# feelerBox1_2_3.net
KiCad netlist of a schematic drawn in EAGLE
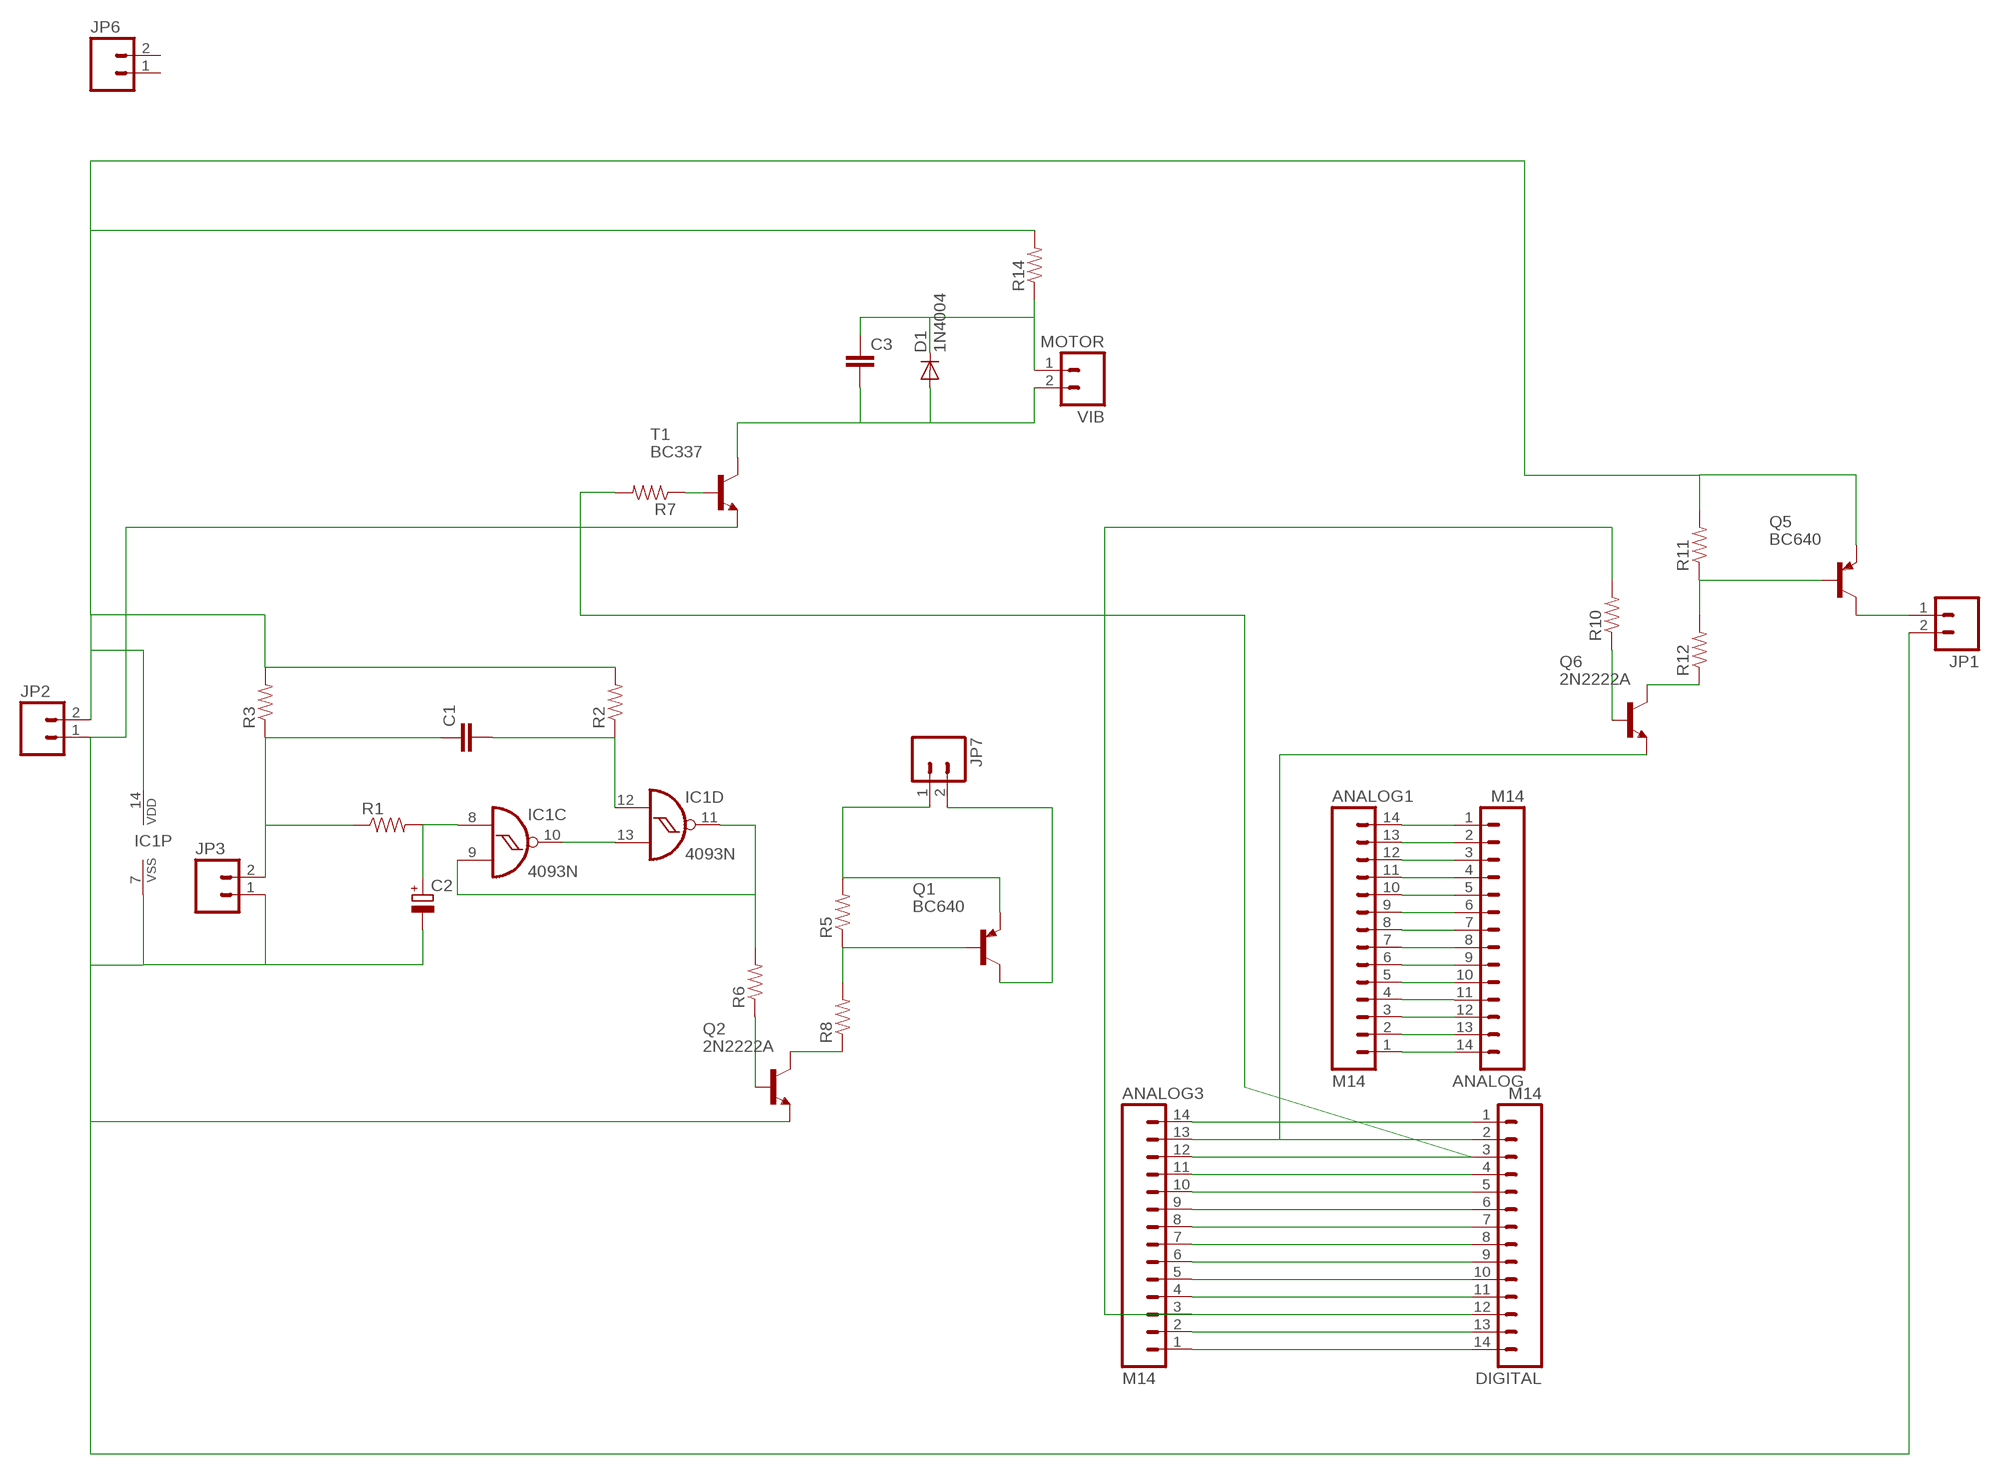
[diagram p0: schematic, sheet 1]

(export (version "E")
  (design (tool "Eeschema 10.0.6"))
  (components
    (comp (ref "ANALOG")
      (value "M14")
      (footprint "eagle-import:1X14")
      (libsource (lib "eagle-import") (part "M14"))
    )
    (comp (ref "ANALOG1")
      (value "M14")
      (footprint "eagle-import:1X14")
      (libsource (lib "eagle-import") (part "M14"))
    )
    (comp (ref "ANALOG3")
      (value "M14")
      (footprint "eagle-import:1X14")
      (libsource (lib "eagle-import") (part "M14"))
    )
    (comp (ref "C1")
      (value "0.1UF-50V-20%(PTH)KIT-EZ")
      (footprint "eagle-import:CAP-PTH-SMALL-KIT")
      (libsource (lib "eagle-import") (part "0.1UF-50V-20%(PTH)KIT-EZ"))
    )
    (comp (ref "C2")
      (value "CPOL-EUE2.5-5")
      (footprint "eagle-import:E2,5-5")
      (libsource (lib "eagle-import") (part "CPOL-EUE2.5-5"))
    )
    (comp (ref "C3")
      (value "CAPKIT")
      (footprint "eagle-import:CAP-PTH-SMALL-KIT")
      (libsource (lib "eagle-import") (part "CAPKIT"))
    )
    (comp (ref "D1")
      (value "1N4004")
      (footprint "eagle-import:DO41-10")
      (libsource (lib "eagle-import") (part "1N4004"))
    )
    (comp (ref "DIGITAL")
      (value "M14")
      (footprint "eagle-import:1X14")
      (libsource (lib "eagle-import") (part "M14"))
    )
    (comp (ref "IC1")
      (value "4093N")
      (footprint "eagle-import:DIL14")
      (libsource (lib "eagle-import") (part "4093N"))
    )
    (comp (ref "JP1")
      (value "M02PTH")
      (footprint "eagle-import:1X02")
      (libsource (lib "eagle-import") (part "M02PTH"))
    )
    (comp (ref "JP2")
      (value "M02PTH")
      (footprint "eagle-import:1X02")
      (libsource (lib "eagle-import") (part "M02PTH"))
    )
    (comp (ref "JP3")
      (value "M02PTH")
      (footprint "eagle-import:1X02")
      (libsource (lib "eagle-import") (part "M02PTH"))
    )
    (comp (ref "JP6")
      (value "M02PTH")
      (footprint "eagle-import:1X02")
      (libsource (lib "eagle-import") (part "M02PTH"))
    )
    (comp (ref "JP7")
      (value "M02PTH")
      (footprint "eagle-import:1X02")
      (libsource (lib "eagle-import") (part "M02PTH"))
    )
    (comp (ref "Q1")
      (value "BC640")
      (footprint "eagle-import:TO92-BCE")
      (libsource (lib "eagle-import") (part "BC640"))
    )
    (comp (ref "Q2")
      (value "2N2222A")
      (footprint "eagle-import:TO18")
      (libsource (lib "eagle-import") (part "2N2222A"))
    )
    (comp (ref "Q5")
      (value "BC640")
      (footprint "eagle-import:TO92-BCE")
      (libsource (lib "eagle-import") (part "BC640"))
    )
    (comp (ref "Q6")
      (value "2N2222A")
      (footprint "eagle-import:TO18")
      (libsource (lib "eagle-import") (part "2N2222A"))
    )
    (comp (ref "R1")
      (value "RESISTORAXIAL-0.3")
      (footprint "eagle-import:AXIAL-0.3")
      (libsource (lib "eagle-import") (part "RESISTORAXIAL-0.3"))
    )
    (comp (ref "R2")
      (value "RESISTORAXIAL-0.3")
      (footprint "eagle-import:AXIAL-0.3")
      (libsource (lib "eagle-import") (part "RESISTORAXIAL-0.3"))
    )
    (comp (ref "R3")
      (value "RESISTORAXIAL-0.3")
      (footprint "eagle-import:AXIAL-0.3")
      (libsource (lib "eagle-import") (part "RESISTORAXIAL-0.3"))
    )
    (comp (ref "R5")
      (value "RESISTORPTH-1/4W-VERT")
      (footprint "eagle-import:AXIAL-0.1")
      (libsource (lib "eagle-import") (part "RESISTORPTH-1/4W-VERT"))
    )
    (comp (ref "R6")
      (value "RESISTORAXIAL-0.3")
      (footprint "eagle-import:AXIAL-0.3")
      (libsource (lib "eagle-import") (part "RESISTORAXIAL-0.3"))
    )
    (comp (ref "R7")
      (value "RESISTORAXIAL-0.3")
      (footprint "eagle-import:AXIAL-0.3")
      (libsource (lib "eagle-import") (part "RESISTORAXIAL-0.3"))
    )
    (comp (ref "R8")
      (value "RESISTORAXIAL-0.3")
      (footprint "eagle-import:AXIAL-0.3")
      (libsource (lib "eagle-import") (part "RESISTORAXIAL-0.3"))
    )
    (comp (ref "R10")
      (value "RESISTORPTH-1/4W-VERT")
      (footprint "eagle-import:AXIAL-0.1")
      (libsource (lib "eagle-import") (part "RESISTORPTH-1/4W-VERT"))
    )
    (comp (ref "R11")
      (value "RESISTORPTH-1/4W-VERT")
      (footprint "eagle-import:AXIAL-0.1")
      (libsource (lib "eagle-import") (part "RESISTORPTH-1/4W-VERT"))
    )
    (comp (ref "R12")
      (value "RESISTORPTH-1/4W-VERT")
      (footprint "eagle-import:AXIAL-0.1")
      (libsource (lib "eagle-import") (part "RESISTORPTH-1/4W-VERT"))
    )
    (comp (ref "R14")
      (value "RESISTORPTH-1/4W-VERT")
      (footprint "eagle-import:AXIAL-0.1")
      (libsource (lib "eagle-import") (part "RESISTORPTH-1/4W-VERT"))
    )
    (comp (ref "T1")
      (value "BC337")
      (footprint "eagle-import:TO92")
      (libsource (lib "eagle-import") (part "BC337"))
    )
    (comp (ref "VIB")
      (value "MOTOR")
      (footprint "eagle-import:1X02")
      (libsource (lib "eagle-import") (part "M02PTH"))
    )
  )
  (nets
    (net (code "1") (name "Net-(ANALOG-Pad1)") (class "Default")
      (node (ref "ANALOG") (pin "1") (pinfunction "1_1") (pintype "passive"))
      (node (ref "ANALOG1") (pin "14") (pinfunction "14_14") (pintype "passive"))
    )
    (net (code "2") (name "Net-(ANALOG-Pad2)") (class "Default")
      (node (ref "ANALOG") (pin "2") (pinfunction "2_2") (pintype "passive"))
      (node (ref "ANALOG1") (pin "13") (pinfunction "13_13") (pintype "passive"))
    )
    (net (code "3") (name "Net-(ANALOG-Pad3)") (class "Default")
      (node (ref "ANALOG") (pin "3") (pinfunction "3_3") (pintype "passive"))
      (node (ref "ANALOG1") (pin "12") (pinfunction "12_12") (pintype "passive"))
    )
    (net (code "4") (name "Net-(ANALOG-Pad4)") (class "Default")
      (node (ref "ANALOG") (pin "4") (pinfunction "4_4") (pintype "passive"))
      (node (ref "ANALOG1") (pin "11") (pinfunction "11_11") (pintype "passive"))
    )
    (net (code "5") (name "Net-(ANALOG-Pad5)") (class "Default")
      (node (ref "ANALOG") (pin "5") (pinfunction "5_5") (pintype "passive"))
      (node (ref "ANALOG1") (pin "10") (pinfunction "10_10") (pintype "passive"))
    )
    (net (code "6") (name "Net-(ANALOG-Pad6)") (class "Default")
      (node (ref "ANALOG") (pin "6") (pinfunction "6_6") (pintype "passive"))
      (node (ref "ANALOG1") (pin "9") (pinfunction "9_9") (pintype "passive"))
    )
    (net (code "7") (name "Net-(ANALOG-Pad7)") (class "Default")
      (node (ref "ANALOG") (pin "7") (pinfunction "7_7") (pintype "passive"))
      (node (ref "ANALOG1") (pin "8") (pinfunction "8_8") (pintype "passive"))
    )
    (net (code "8") (name "Net-(ANALOG-Pad8)") (class "Default")
      (node (ref "ANALOG") (pin "8") (pinfunction "8_8") (pintype "passive"))
      (node (ref "ANALOG1") (pin "7") (pinfunction "7_7") (pintype "passive"))
    )
    (net (code "9") (name "Net-(ANALOG-Pad9)") (class "Default")
      (node (ref "ANALOG") (pin "9") (pinfunction "9_9") (pintype "passive"))
      (node (ref "ANALOG1") (pin "6") (pinfunction "6_6") (pintype "passive"))
    )
    (net (code "10") (name "Net-(ANALOG-Pad10)") (class "Default")
      (node (ref "ANALOG") (pin "10") (pinfunction "10_10") (pintype "passive"))
      (node (ref "ANALOG1") (pin "5") (pinfunction "5_5") (pintype "passive"))
    )
    (net (code "11") (name "Net-(ANALOG-Pad11)") (class "Default")
      (node (ref "ANALOG") (pin "11") (pinfunction "11_11") (pintype "passive"))
      (node (ref "ANALOG1") (pin "4") (pinfunction "4_4") (pintype "passive"))
    )
    (net (code "12") (name "Net-(ANALOG-Pad12)") (class "Default")
      (node (ref "ANALOG") (pin "12") (pinfunction "12_12") (pintype "passive"))
      (node (ref "ANALOG1") (pin "3") (pinfunction "3_3") (pintype "passive"))
    )
    (net (code "13") (name "Net-(ANALOG-Pad13)") (class "Default")
      (node (ref "ANALOG") (pin "13") (pinfunction "13_13") (pintype "passive"))
      (node (ref "ANALOG1") (pin "2") (pinfunction "2_2") (pintype "passive"))
    )
    (net (code "14") (name "Net-(ANALOG-Pad14)") (class "Default")
      (node (ref "ANALOG") (pin "14") (pinfunction "14_14") (pintype "passive"))
      (node (ref "ANALOG1") (pin "1") (pinfunction "1_1") (pintype "passive"))
    )
    (net (code "15") (name "Net-(ANALOG3-Pad1)") (class "Default")
      (node (ref "ANALOG3") (pin "1") (pinfunction "1_1") (pintype "passive"))
      (node (ref "DIGITAL") (pin "14") (pinfunction "14_14") (pintype "passive"))
    )
    (net (code "16") (name "Net-(ANALOG3-Pad2)") (class "Default")
      (node (ref "ANALOG3") (pin "2") (pinfunction "2_2") (pintype "passive"))
      (node (ref "DIGITAL") (pin "13") (pinfunction "13_13") (pintype "passive"))
    )
    (net (code "17") (name "Net-(ANALOG3-Pad4)") (class "Default")
      (node (ref "ANALOG3") (pin "4") (pinfunction "4_4") (pintype "passive"))
      (node (ref "DIGITAL") (pin "11") (pinfunction "11_11") (pintype "passive"))
    )
    (net (code "18") (name "Net-(ANALOG3-Pad5)") (class "Default")
      (node (ref "ANALOG3") (pin "5") (pinfunction "5_5") (pintype "passive"))
      (node (ref "DIGITAL") (pin "10") (pinfunction "10_10") (pintype "passive"))
    )
    (net (code "19") (name "Net-(ANALOG3-Pad6)") (class "Default")
      (node (ref "ANALOG3") (pin "6") (pinfunction "6_6") (pintype "passive"))
      (node (ref "DIGITAL") (pin "9") (pinfunction "9_9") (pintype "passive"))
    )
    (net (code "20") (name "Net-(ANALOG3-Pad7)") (class "Default")
      (node (ref "ANALOG3") (pin "7") (pinfunction "7_7") (pintype "passive"))
      (node (ref "DIGITAL") (pin "8") (pinfunction "8_8") (pintype "passive"))
    )
    (net (code "21") (name "Net-(ANALOG3-Pad8)") (class "Default")
      (node (ref "ANALOG3") (pin "8") (pinfunction "8_8") (pintype "passive"))
      (node (ref "DIGITAL") (pin "7") (pinfunction "7_7") (pintype "passive"))
    )
    (net (code "22") (name "Net-(ANALOG3-Pad9)") (class "Default")
      (node (ref "ANALOG3") (pin "9") (pinfunction "9_9") (pintype "passive"))
      (node (ref "DIGITAL") (pin "6") (pinfunction "6_6") (pintype "passive"))
    )
    (net (code "23") (name "Net-(ANALOG3-Pad10)") (class "Default")
      (node (ref "ANALOG3") (pin "10") (pinfunction "10_10") (pintype "passive"))
      (node (ref "DIGITAL") (pin "5") (pinfunction "5_5") (pintype "passive"))
    )
    (net (code "24") (name "Net-(ANALOG3-Pad11)") (class "Default")
      (node (ref "ANALOG3") (pin "11") (pinfunction "11_11") (pintype "passive"))
      (node (ref "DIGITAL") (pin "4") (pinfunction "4_4") (pintype "passive"))
    )
    (net (code "25") (name "Net-(ANALOG3-Pad14)") (class "Default")
      (node (ref "ANALOG3") (pin "14") (pinfunction "14_14") (pintype "passive"))
      (node (ref "DIGITAL") (pin "1") (pinfunction "1_1") (pintype "passive"))
    )
    (net (code "26") (name "Net-(IC1C-I0)") (class "Default")
      (node (ref "C2") (pin "+") (pinfunction "+_+") (pintype "passive"))
      (node (ref "IC1") (pin "8") (pinfunction "I0_8") (pintype "input"))
      (node (ref "R1") (pin "P$2") (pinfunction "2_P$2") (pintype "passive"))
    )
    (net (code "27") (name "Net-(IC1C-I1)") (class "Default")
      (node (ref "IC1") (pin "11") (pinfunction "O_11") (pintype "output"))
      (node (ref "IC1") (pin "9") (pinfunction "I1_9") (pintype "input"))
      (node (ref "R6") (pin "P$2") (pinfunction "2_P$2") (pintype "passive"))
    )
    (net (code "28") (name "Net-(IC1C-O)") (class "Default")
      (node (ref "IC1") (pin "10") (pinfunction "O_10") (pintype "output"))
      (node (ref "IC1") (pin "13") (pinfunction "I1_13") (pintype "input"))
    )
    (net (code "29") (name "Net-(IC1D-I0)") (class "Default")
      (node (ref "C1") (pin "2") (pinfunction "2_2") (pintype "passive"))
      (node (ref "IC1") (pin "12") (pinfunction "I0_12") (pintype "input"))
      (node (ref "R2") (pin "P$1") (pinfunction "1_P$1") (pintype "passive"))
    )
    (net (code "30") (name "Net-(IC1E-VDD)") (class "Default")
      (node (ref "IC1") (pin "14") (pinfunction "VDD_14") (pintype "power_in"))
      (node (ref "JP2") (pin "2") (pinfunction "2_2") (pintype "passive"))
      (node (ref "Q5") (pin "E") (pinfunction "E_E") (pintype "passive"))
      (node (ref "R11") (pin "P$2") (pinfunction "2_P$2") (pintype "passive"))
      (node (ref "R14") (pin "P$2") (pinfunction "2_P$2") (pintype "passive"))
      (node (ref "R2") (pin "P$2") (pinfunction "2_P$2") (pintype "passive"))
      (node (ref "R3") (pin "P$2") (pinfunction "2_P$2") (pintype "passive"))
    )
    (net (code "31") (name "Net-(IC1E-VSS)") (class "Default")
      (node (ref "C2") (pin "-") (pinfunction "-_-") (pintype "passive"))
      (node (ref "IC1") (pin "7") (pinfunction "VSS_7") (pintype "power_in"))
      (node (ref "JP1") (pin "2") (pinfunction "2_2") (pintype "passive"))
      (node (ref "JP2") (pin "1") (pinfunction "1_1") (pintype "passive"))
      (node (ref "JP3") (pin "1") (pinfunction "1_1") (pintype "passive"))
      (node (ref "Q2") (pin "1") (pinfunction "E_1") (pintype "passive"))
      (node (ref "T1") (pin "1") (pinfunction "E_1") (pintype "passive"))
    )
    (net (code "32") (name "Net-(JP1-Pad1)") (class "Default")
      (node (ref "JP1") (pin "1") (pinfunction "1_1") (pintype "passive"))
      (node (ref "Q5") (pin "C") (pinfunction "C_C") (pintype "passive"))
    )
    (net (code "33") (name "Net-(JP7-Pad2)") (class "Default")
      (node (ref "JP7") (pin "2") (pinfunction "2_2") (pintype "passive"))
      (node (ref "Q1") (pin "C") (pinfunction "C_C") (pintype "passive"))
    )
    (net (code "34") (name "Net-(Q2-B)") (class "Default")
      (node (ref "Q2") (pin "2") (pinfunction "B_2") (pintype "passive"))
      (node (ref "R6") (pin "P$1") (pinfunction "1_P$1") (pintype "passive"))
    )
    (net (code "35") (name "Net-(Q2-C)") (class "Default")
      (node (ref "Q2") (pin "3") (pinfunction "C_3") (pintype "passive"))
      (node (ref "R8") (pin "P$1") (pinfunction "1_P$1") (pintype "passive"))
    )
    (net (code "36") (name "Net-(Q6-B)") (class "Default")
      (node (ref "Q6") (pin "2") (pinfunction "B_2") (pintype "passive"))
      (node (ref "R10") (pin "P$1") (pinfunction "1_P$1") (pintype "passive"))
    )
    (net (code "37") (name "Net-(Q6-C)") (class "Default")
      (node (ref "Q6") (pin "3") (pinfunction "C_3") (pintype "passive"))
      (node (ref "R12") (pin "P$1") (pinfunction "1_P$1") (pintype "passive"))
    )
    (net (code "38") (name "Net-(Q6-E)") (class "Default")
      (node (ref "ANALOG3") (pin "13") (pinfunction "13_13") (pintype "passive"))
      (node (ref "DIGITAL") (pin "2") (pinfunction "2_2") (pintype "passive"))
      (node (ref "Q6") (pin "1") (pinfunction "E_1") (pintype "passive"))
    )
    (net (code "39") (name "Net-(R1-1)") (class "Default")
      (node (ref "C1") (pin "1") (pinfunction "1_1") (pintype "passive"))
      (node (ref "JP3") (pin "2") (pinfunction "2_2") (pintype "passive"))
      (node (ref "R1") (pin "P$1") (pinfunction "1_P$1") (pintype "passive"))
      (node (ref "R3") (pin "P$1") (pinfunction "1_P$1") (pintype "passive"))
    )
    (net (code "40") (name "Net-(R5-1)") (class "Default")
      (node (ref "Q1") (pin "B") (pinfunction "B_B") (pintype "passive"))
      (node (ref "R5") (pin "P$1") (pinfunction "1_P$1") (pintype "passive"))
      (node (ref "R8") (pin "P$2") (pinfunction "2_P$2") (pintype "passive"))
    )
    (net (code "41") (name "Net-(R5-2)") (class "Default")
      (node (ref "JP7") (pin "1") (pinfunction "1_1") (pintype "passive"))
      (node (ref "Q1") (pin "E") (pinfunction "E_E") (pintype "passive"))
      (node (ref "R5") (pin "P$2") (pinfunction "2_P$2") (pintype "passive"))
    )
    (net (code "42") (name "Net-(R7-1)") (class "Default")
      (node (ref "R7") (pin "P$1") (pinfunction "1_P$1") (pintype "passive"))
      (node (ref "T1") (pin "2") (pinfunction "B_2") (pintype "passive"))
    )
    (net (code "43") (name "Net-(R7-2)") (class "Default")
      (node (ref "ANALOG3") (pin "12") (pinfunction "12_12") (pintype "passive"))
      (node (ref "DIGITAL") (pin "3") (pinfunction "3_3") (pintype "passive"))
      (node (ref "R7") (pin "P$2") (pinfunction "2_P$2") (pintype "passive"))
    )
    (net (code "44") (name "Net-(R10-2)") (class "Default")
      (node (ref "ANALOG3") (pin "3") (pinfunction "3_3") (pintype "passive"))
      (node (ref "DIGITAL") (pin "12") (pinfunction "12_12") (pintype "passive"))
      (node (ref "R10") (pin "P$2") (pinfunction "2_P$2") (pintype "passive"))
    )
    (net (code "45") (name "Net-(R11-1)") (class "Default")
      (node (ref "Q5") (pin "B") (pinfunction "B_B") (pintype "passive"))
      (node (ref "R11") (pin "P$1") (pinfunction "1_P$1") (pintype "passive"))
      (node (ref "R12") (pin "P$2") (pinfunction "2_P$2") (pintype "passive"))
    )
    (net (code "46") (name "Net-(R14-1)") (class "Default")
      (node (ref "C3") (pin "1") (pinfunction "1_1") (pintype "passive"))
      (node (ref "D1") (pin "C") (pinfunction "C_C") (pintype "passive"))
      (node (ref "R14") (pin "P$1") (pinfunction "1_P$1") (pintype "passive"))
      (node (ref "VIB") (pin "1") (pinfunction "1_1") (pintype "passive"))
    )
    (net (code "47") (name "Net-(T1-C)") (class "Default")
      (node (ref "C3") (pin "2") (pinfunction "2_2") (pintype "passive"))
      (node (ref "D1") (pin "A") (pinfunction "A_A") (pintype "passive"))
      (node (ref "T1") (pin "3") (pinfunction "C_3") (pintype "passive"))
      (node (ref "VIB") (pin "2") (pinfunction "2_2") (pintype "passive"))
    )
    (net (code "48") (name "unconnected-(JP6-Pad1)") (class "Default")
      (node (ref "JP6") (pin "1") (pinfunction "1_1") (pintype "passive"))
    )
    (net (code "49") (name "unconnected-(JP6-Pad2)") (class "Default")
      (node (ref "JP6") (pin "2") (pinfunction "2_2") (pintype "passive"))
    )
  )
)
